# 140321_AriloTX_REV2_0_0.net
KiCad netlist of a schematic drawn in EAGLE
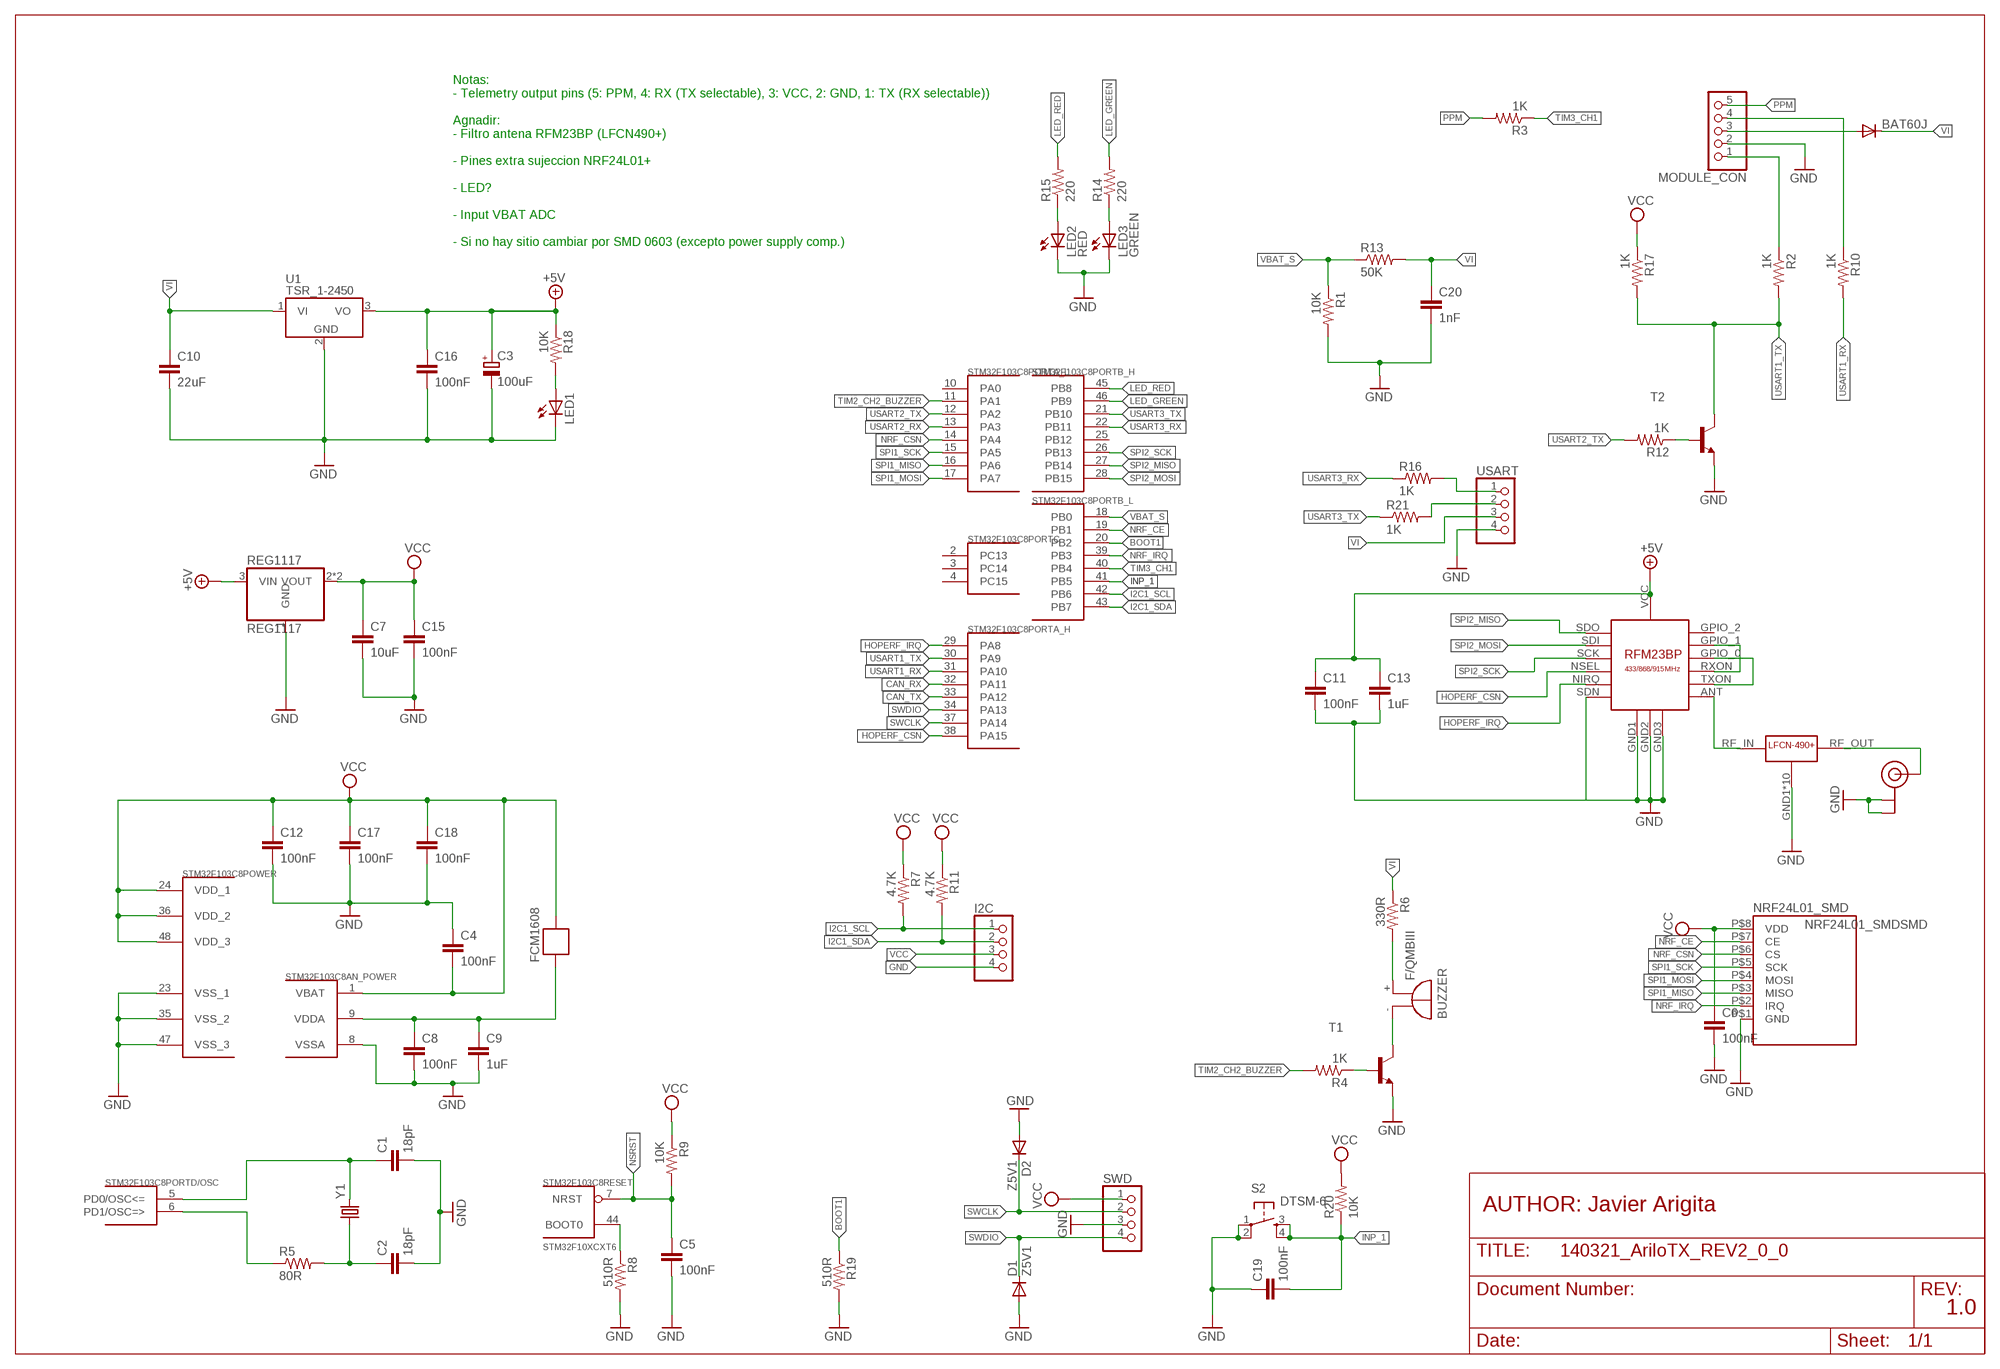
[diagram p0: schematic, sheet 1]

(export (version "E")
  (design (tool "Eeschema 10.0.6"))
  (components
    (comp (ref "BAT60J")
      (value "DIODE-SOD323-R")
      (footprint "eagle-import:SOD323-R")
      (libsource (lib "eagle-import") (part "DIODE-SOD323-R"))
    )
    (comp (ref "BUZZER")
      (value "F/QMBIII")
      (footprint "eagle-import:F_QMBIII")
      (libsource (lib "eagle-import") (part "F/QMBIII"))
    )
    (comp (ref "C1")
      (value "18pF")
      (footprint "eagle-import:C0805")
      (libsource (lib "eagle-import") (part "C-EUC0805"))
    )
    (comp (ref "C2")
      (value "18pF")
      (footprint "eagle-import:C0805")
      (libsource (lib "eagle-import") (part "C-EUC0805"))
    )
    (comp (ref "C3")
      (value "100uF")
      (footprint "eagle-import:SMC_B")
      (libsource (lib "eagle-import") (part "CPOL-EUSMCB"))
    )
    (comp (ref "C4")
      (value "100nF")
      (footprint "eagle-import:C0805")
      (libsource (lib "eagle-import") (part "C-EUC0805"))
    )
    (comp (ref "C5")
      (value "100nF")
      (footprint "eagle-import:C0805")
      (libsource (lib "eagle-import") (part "C-EUC0805"))
    )
    (comp (ref "C6")
      (value "100nF")
      (footprint "eagle-import:C0805")
      (libsource (lib "eagle-import") (part "C-EUC0805"))
    )
    (comp (ref "C7")
      (value "10uF")
      (footprint "eagle-import:C0805")
      (libsource (lib "eagle-import") (part "C-EUC0805"))
    )
    (comp (ref "C8")
      (value "100nF")
      (footprint "eagle-import:C0805")
      (libsource (lib "eagle-import") (part "C-EUC0805"))
    )
    (comp (ref "C9")
      (value "1uF")
      (footprint "eagle-import:C3216")
      (libsource (lib "eagle-import") (part "resistor_C-EUC3216"))
    )
    (comp (ref "C10")
      (value "22uF")
      (footprint "eagle-import:C3216")
      (libsource (lib "eagle-import") (part "resistor_C-EUC3216"))
    )
    (comp (ref "C11")
      (value "100nF")
      (footprint "eagle-import:C0805")
      (libsource (lib "eagle-import") (part "C-EUC0805"))
    )
    (comp (ref "C12")
      (value "100nF")
      (footprint "eagle-import:C0805")
      (libsource (lib "eagle-import") (part "C-EUC0805"))
    )
    (comp (ref "C13")
      (value "1uF")
      (footprint "eagle-import:C3216")
      (libsource (lib "eagle-import") (part "resistor_C-EUC3216"))
    )
    (comp (ref "C15")
      (value "100nF")
      (footprint "eagle-import:C0805")
      (libsource (lib "eagle-import") (part "C-EUC0805"))
    )
    (comp (ref "C16")
      (value "100nF")
      (footprint "eagle-import:C0805")
      (libsource (lib "eagle-import") (part "C-EUC0805"))
    )
    (comp (ref "C17")
      (value "100nF")
      (footprint "eagle-import:C0805")
      (libsource (lib "eagle-import") (part "C-EUC0805"))
    )
    (comp (ref "C18")
      (value "100nF")
      (footprint "eagle-import:C0805")
      (libsource (lib "eagle-import") (part "C-EUC0805"))
    )
    (comp (ref "C19")
      (value "100nF")
      (footprint "eagle-import:C0805")
      (libsource (lib "eagle-import") (part "C-EUC0805"))
    )
    (comp (ref "C20")
      (value "1nF")
      (footprint "eagle-import:C0805")
      (libsource (lib "eagle-import") (part "C-EUC0805"))
    )
    (comp (ref "D1")
      (value "Z5V1")
      (footprint "eagle-import:SOD323-R")
      (libsource (lib "eagle-import") (part "DIODE-SOD323-R"))
    )
    (comp (ref "D2")
      (value "Z5V1")
      (footprint "eagle-import:SOD323-R")
      (libsource (lib "eagle-import") (part "DIODE-SOD323-R"))
    )
    (comp (ref "FCM1608")
      (value "FERRITE-BEAD")
      (footprint "eagle-import:R0603")
      (libsource (lib "eagle-import") (part "FERRITE-BEAD"))
    )
    (comp (ref "I2C")
      (value "PINHD-1X4")
      (footprint "eagle-import:1X04")
      (libsource (lib "eagle-import") (part "PINHD-1X4"))
    )
    (comp (ref "LED1")
      (value "LED0805")
      (footprint "eagle-import:CHIPLED_0805")
      (libsource (lib "eagle-import") (part "LED0805"))
    )
    (comp (ref "LED2")
      (value "RED")
      (footprint "eagle-import:CHIP-LED0805")
      (libsource (lib "eagle-import") (part "LEDCHIP-LED0805"))
    )
    (comp (ref "LED3")
      (value "GREEN")
      (footprint "eagle-import:CHIP-LED0805")
      (libsource (lib "eagle-import") (part "LEDCHIP-LED0805"))
    )
    (comp (ref "MODULE_CON")
      (value "PINHD-1X5")
      (footprint "eagle-import:1X05")
      (libsource (lib "eagle-import") (part "PINHD-1X5"))
    )
    (comp (ref "NRF24L01_SMD")
      (value "NRF24L01_SMDSMD")
      (footprint "eagle-import:NRF24L01_SMD")
      (libsource (lib "eagle-import") (part "NRF24L01_SMDSMD"))
    )
    (comp (ref "R1")
      (value "10K")
      (footprint "eagle-import:R0805")
      (libsource (lib "eagle-import") (part "RESISTOR0805"))
    )
    (comp (ref "R2")
      (value "1K")
      (footprint "eagle-import:R0805")
      (libsource (lib "eagle-import") (part "RESISTOR0805"))
    )
    (comp (ref "R3")
      (value "1K")
      (footprint "eagle-import:R0805")
      (libsource (lib "eagle-import") (part "RESISTOR0805"))
    )
    (comp (ref "R4")
      (value "1K")
      (footprint "eagle-import:R0805")
      (libsource (lib "eagle-import") (part "RESISTOR0805"))
    )
    (comp (ref "R5")
      (value "80R")
      (footprint "eagle-import:R0805")
      (libsource (lib "eagle-import") (part "RESISTOR0805"))
    )
    (comp (ref "R6")
      (value "330R")
      (footprint "eagle-import:R0805")
      (libsource (lib "eagle-import") (part "RESISTOR0805"))
    )
    (comp (ref "R7")
      (value "4.7K")
      (footprint "eagle-import:R0805")
      (libsource (lib "eagle-import") (part "RESISTOR0805"))
    )
    (comp (ref "R8")
      (value "510R")
      (footprint "eagle-import:R0805")
      (libsource (lib "eagle-import") (part "RESISTOR0805"))
    )
    (comp (ref "R9")
      (value "10K")
      (footprint "eagle-import:R0805")
      (libsource (lib "eagle-import") (part "RESISTOR0805"))
    )
    (comp (ref "R10")
      (value "1K")
      (footprint "eagle-import:R0805")
      (libsource (lib "eagle-import") (part "RESISTOR0805"))
    )
    (comp (ref "R11")
      (value "4.7K")
      (footprint "eagle-import:R0805")
      (libsource (lib "eagle-import") (part "RESISTOR0805"))
    )
    (comp (ref "R12")
      (value "1K")
      (footprint "eagle-import:R0805")
      (libsource (lib "eagle-import") (part "RESISTOR0805"))
    )
    (comp (ref "R13")
      (value "50K")
      (footprint "eagle-import:R0805")
      (libsource (lib "eagle-import") (part "RESISTOR0805"))
    )
    (comp (ref "R14")
      (value "220")
      (footprint "eagle-import:R0805")
      (libsource (lib "eagle-import") (part "RESISTOR0805"))
    )
    (comp (ref "R15")
      (value "220")
      (footprint "eagle-import:R0805")
      (libsource (lib "eagle-import") (part "RESISTOR0805"))
    )
    (comp (ref "R16")
      (value "1K")
      (footprint "eagle-import:R0805")
      (libsource (lib "eagle-import") (part "RESISTOR0805"))
    )
    (comp (ref "R17")
      (value "1K")
      (footprint "eagle-import:R0805")
      (libsource (lib "eagle-import") (part "RESISTOR0805"))
    )
    (comp (ref "R18")
      (value "10K")
      (footprint "eagle-import:R0805")
      (libsource (lib "eagle-import") (part "RESISTOR0805"))
    )
    (comp (ref "R19")
      (value "510R")
      (footprint "eagle-import:R0805")
      (libsource (lib "eagle-import") (part "RESISTOR0805"))
    )
    (comp (ref "R20")
      (value "10K")
      (footprint "eagle-import:R0805")
      (libsource (lib "eagle-import") (part "RESISTOR0805"))
    )
    (comp (ref "R21")
      (value "1K")
      (footprint "eagle-import:R0805")
      (libsource (lib "eagle-import") (part "RESISTOR0805"))
    )
    (comp (ref "REG1117")
      (value "REG1117")
      (footprint "eagle-import:SOT223")
      (libsource (lib "eagle-import") (part "REG1117"))
    )
    (comp (ref "S2")
      (value "DTSM-6")
      (footprint "eagle-import:DTSM-6")
      (libsource (lib "eagle-import") (part "DTSM-6"))
    )
    (comp (ref "STM32F103C8")
      (value "STM32F10XCXT6")
      (footprint "eagle-import:TQFP48")
      (libsource (lib "eagle-import") (part "STM32F10XCXT6"))
    )
    (comp (ref "SWD")
      (value "PINHD-1X4")
      (footprint "eagle-import:1X04")
      (libsource (lib "eagle-import") (part "PINHD-1X4"))
    )
    (comp (ref "T1")
      (value "BC848-NPN-SOT23-BEC")
      (footprint "eagle-import:SOT23-BEC")
      (libsource (lib "eagle-import") (part "-NPN-SOT23-BECBC848"))
    )
    (comp (ref "T2")
      (value "BC848-NPN-SOT23-BEC")
      (footprint "eagle-import:SOT23-BEC")
      (libsource (lib "eagle-import") (part "-NPN-SOT23-BECBC848"))
    )
    (comp (ref "U$1")
      (value "RFM23BP")
      (footprint "eagle-import:RFM23BP")
      (libsource (lib "eagle-import") (part "RFM23BP"))
    )
    (comp (ref "U$2")
      (value "LFCN490+")
      (footprint "eagle-import:LFCN490+")
      (libsource (lib "eagle-import") (part "LFCN490+"))
    )
    (comp (ref "U$3")
      (value "U.FL")
      (footprint "eagle-import:U.FL")
      (libsource (lib "eagle-import") (part "U.FL"))
    )
    (comp (ref "U1")
      (value "TSR_1-2450")
      (footprint "eagle-import:TSR-1")
      (libsource (lib "eagle-import") (part "TSR_1-2450"))
    )
    (comp (ref "USART")
      (value "PINHD-1X4")
      (footprint "eagle-import:1X04")
      (libsource (lib "eagle-import") (part "PINHD-1X4"))
    )
    (comp (ref "Y1")
      (value "CRYSTAL5X3")
      (footprint "eagle-import:CRYSTAL-SMD-5X3")
      (libsource (lib "eagle-import") (part "CRYSTAL5X3"))
    )
  )
  (nets
    (net (code "1") (name "+5V") (class "Default")
      (node (ref "C11") (pin "1") (pinfunction "1_1") (pintype "passive"))
      (node (ref "C13") (pin "1") (pinfunction "1_1") (pintype "passive"))
      (node (ref "C16") (pin "1") (pinfunction "1_1") (pintype "passive"))
      (node (ref "C3") (pin "+") (pinfunction "+_+") (pintype "passive"))
      (node (ref "R18") (pin "1") (pinfunction "1_1") (pintype "passive"))
      (node (ref "REG1117") (pin "3") (pinfunction "VIN_3") (pintype "input"))
      (node (ref "U$1") (pin "VCC") (pinfunction "VCC_VCC") (pintype "power_in"))
      (node (ref "U1") (pin "3") (pinfunction "VO_3") (pintype "power_in"))
    )
    (net (code "2") (name "BOOT1") (class "Default")
      (node (ref "R19") (pin "1") (pinfunction "1_1") (pintype "passive"))
      (node (ref "STM32F103C8") (pin "20") (pinfunction "PB2_20") (pintype "bidirectional"))
    )
    (net (code "3") (name "CAN_RX") (class "Default")
      (node (ref "STM32F103C8") (pin "32") (pinfunction "PA11_32") (pintype "bidirectional"))
    )
    (net (code "4") (name "CAN_TX") (class "Default")
      (node (ref "STM32F103C8") (pin "33") (pinfunction "PA12_33") (pintype "bidirectional"))
    )
    (net (code "5") (name "GND") (class "Default")
      (node (ref "C1") (pin "2") (pinfunction "2_2") (pintype "passive"))
      (node (ref "C10") (pin "2") (pinfunction "2_2") (pintype "passive"))
      (node (ref "C11") (pin "2") (pinfunction "2_2") (pintype "passive"))
      (node (ref "C12") (pin "2") (pinfunction "2_2") (pintype "passive"))
      (node (ref "C13") (pin "2") (pinfunction "2_2") (pintype "passive"))
      (node (ref "C15") (pin "2") (pinfunction "2_2") (pintype "passive"))
      (node (ref "C16") (pin "2") (pinfunction "2_2") (pintype "passive"))
      (node (ref "C17") (pin "2") (pinfunction "2_2") (pintype "passive"))
      (node (ref "C18") (pin "2") (pinfunction "2_2") (pintype "passive"))
      (node (ref "C19") (pin "1") (pinfunction "1_1") (pintype "passive"))
      (node (ref "C2") (pin "2") (pinfunction "2_2") (pintype "passive"))
      (node (ref "C20") (pin "2") (pinfunction "2_2") (pintype "passive"))
      (node (ref "C3") (pin "-") (pinfunction "-_-") (pintype "passive"))
      (node (ref "C4") (pin "1") (pinfunction "1_1") (pintype "passive"))
      (node (ref "C5") (pin "2") (pinfunction "2_2") (pintype "passive"))
      (node (ref "C6") (pin "2") (pinfunction "2_2") (pintype "passive"))
      (node (ref "C7") (pin "2") (pinfunction "2_2") (pintype "passive"))
      (node (ref "C8") (pin "2") (pinfunction "2_2") (pintype "passive"))
      (node (ref "C9") (pin "2") (pinfunction "2_2") (pintype "passive"))
      (node (ref "D1") (pin "A") (pinfunction "A_A") (pintype "passive"))
      (node (ref "D2") (pin "A") (pinfunction "A_A") (pintype "passive"))
      (node (ref "I2C") (pin "4") (pinfunction "4_4") (pintype "passive"))
      (node (ref "LED1") (pin "C") (pinfunction "C_C") (pintype "passive"))
      (node (ref "LED2") (pin "C") (pinfunction "C_C") (pintype "passive"))
      (node (ref "LED3") (pin "C") (pinfunction "C_C") (pintype "passive"))
      (node (ref "MODULE_CON") (pin "2") (pinfunction "2_2") (pintype "passive"))
      (node (ref "NRF24L01_SMD") (pin "P$1") (pinfunction "GND_P$1") (pintype "power_in"))
      (node (ref "R1") (pin "2") (pinfunction "2_2") (pintype "passive"))
      (node (ref "R19") (pin "2") (pinfunction "2_2") (pintype "passive"))
      (node (ref "R8") (pin "2") (pinfunction "2_2") (pintype "passive"))
      (node (ref "REG1117") (pin "1") (pinfunction "GND_1") (pintype "power_in"))
      (node (ref "S2") (pin "1") (pinfunction "1_1") (pintype "passive"))
      (node (ref "S2") (pin "2") (pinfunction "2_2") (pintype "passive"))
      (node (ref "STM32F103C8") (pin "23") (pinfunction "VSS_1_23") (pintype "power_in"))
      (node (ref "STM32F103C8") (pin "35") (pinfunction "VSS_2_35") (pintype "power_in"))
      (node (ref "STM32F103C8") (pin "47") (pinfunction "VSS_3_47") (pintype "power_in"))
      (node (ref "STM32F103C8") (pin "8") (pinfunction "VSSA_8") (pintype "power_in"))
      (node (ref "SWD") (pin "3") (pinfunction "3_3") (pintype "passive"))
      (node (ref "T1") (pin "E") (pinfunction "E_E") (pintype "passive"))
      (node (ref "T2") (pin "E") (pinfunction "E_E") (pintype "passive"))
      (node (ref "U$1") (pin "GND1") (pinfunction "GND1_GND1") (pintype "power_in"))
      (node (ref "U$1") (pin "GND2") (pinfunction "GND2_GND2") (pintype "power_in"))
      (node (ref "U$1") (pin "GND3") (pinfunction "GND3_GND3") (pintype "power_in"))
      (node (ref "U$1") (pin "SDN") (pinfunction "SDN_SDN") (pintype "bidirectional"))
      (node (ref "U$2") (pin "GND1") (pinfunction "GND_GND1") (pintype "bidirectional"))
      (node (ref "U$2") (pin "GND10") (pinfunction "GND_GND10") (pintype "bidirectional"))
      (node (ref "U$2") (pin "GND2") (pinfunction "GND_GND2") (pintype "bidirectional"))
      (node (ref "U$2") (pin "GND3") (pinfunction "GND_GND3") (pintype "bidirectional"))
      (node (ref "U$2") (pin "GND4") (pinfunction "GND_GND4") (pintype "bidirectional"))
      (node (ref "U$2") (pin "GND5") (pinfunction "GND_GND5") (pintype "bidirectional"))
      (node (ref "U$2") (pin "GND6") (pinfunction "GND_GND6") (pintype "bidirectional"))
      (node (ref "U$2") (pin "GND7") (pinfunction "GND_GND7") (pintype "bidirectional"))
      (node (ref "U$2") (pin "GND8") (pinfunction "GND_GND8") (pintype "bidirectional"))
      (node (ref "U$2") (pin "GND9") (pinfunction "GND_GND9") (pintype "bidirectional"))
      (node (ref "U$3") (pin "P$1") (pinfunction "GND_P$1") (pintype "bidirectional"))
      (node (ref "U$3") (pin "P$2") (pinfunction "GND_P$2") (pintype "bidirectional"))
      (node (ref "U1") (pin "2") (pinfunction "GND_2") (pintype "power_in"))
      (node (ref "USART") (pin "4") (pinfunction "4_4") (pintype "passive"))
    )
    (net (code "6") (name "HOPERF_CSN") (class "Default")
      (node (ref "STM32F103C8") (pin "38") (pinfunction "PA15_38") (pintype "bidirectional"))
      (node (ref "U$1") (pin "NSEL") (pinfunction "NSEL_NSEL") (pintype "bidirectional"))
    )
    (net (code "7") (name "HOPERF_IRQ") (class "Default")
      (node (ref "STM32F103C8") (pin "29") (pinfunction "PA8_29") (pintype "bidirectional"))
      (node (ref "U$1") (pin "NIRQ") (pinfunction "NIRQ_NIRQ") (pintype "bidirectional"))
    )
    (net (code "8") (name "I2C1_SCL") (class "Default")
      (node (ref "I2C") (pin "1") (pinfunction "1_1") (pintype "passive"))
      (node (ref "R7") (pin "2") (pinfunction "2_2") (pintype "passive"))
      (node (ref "STM32F103C8") (pin "42") (pinfunction "PB6_42") (pintype "bidirectional"))
    )
    (net (code "9") (name "I2C1_SDA") (class "Default")
      (node (ref "I2C") (pin "2") (pinfunction "2_2") (pintype "passive"))
      (node (ref "R11") (pin "2") (pinfunction "2_2") (pintype "passive"))
      (node (ref "STM32F103C8") (pin "43") (pinfunction "PB7_43") (pintype "bidirectional"))
    )
    (net (code "10") (name "INP_1") (class "Default")
      (node (ref "C19") (pin "2") (pinfunction "2_2") (pintype "passive"))
      (node (ref "R20") (pin "1") (pinfunction "1_1") (pintype "passive"))
      (node (ref "S2") (pin "3") (pinfunction "3_3") (pintype "passive"))
      (node (ref "S2") (pin "4") (pinfunction "4_4") (pintype "passive"))
      (node (ref "STM32F103C8") (pin "41") (pinfunction "PB5_41") (pintype "bidirectional"))
    )
    (net (code "11") (name "LED_GREEN") (class "Default")
      (node (ref "R14") (pin "2") (pinfunction "2_2") (pintype "passive"))
      (node (ref "STM32F103C8") (pin "46") (pinfunction "PB9_46") (pintype "bidirectional"))
    )
    (net (code "12") (name "LED_RED") (class "Default")
      (node (ref "R15") (pin "2") (pinfunction "2_2") (pintype "passive"))
      (node (ref "STM32F103C8") (pin "45") (pinfunction "PB8_45") (pintype "bidirectional"))
    )
    (net (code "13") (name "NRF_CE") (class "Default")
      (node (ref "NRF24L01_SMD") (pin "P$7") (pinfunction "CE_P$7") (pintype "input"))
      (node (ref "STM32F103C8") (pin "19") (pinfunction "PB1_19") (pintype "bidirectional"))
    )
    (net (code "14") (name "NRF_CSN") (class "Default")
      (node (ref "NRF24L01_SMD") (pin "P$6") (pinfunction "CS_P$6") (pintype "input"))
      (node (ref "STM32F103C8") (pin "14") (pinfunction "PA4_14") (pintype "bidirectional"))
    )
    (net (code "15") (name "NRF_IRQ") (class "Default")
      (node (ref "NRF24L01_SMD") (pin "P$2") (pinfunction "IRQ_P$2") (pintype "output"))
      (node (ref "STM32F103C8") (pin "39") (pinfunction "PB3_39") (pintype "bidirectional"))
    )
    (net (code "16") (name "NSRST") (class "Default")
      (node (ref "C5") (pin "1") (pinfunction "1_1") (pintype "passive"))
      (node (ref "R9") (pin "2") (pinfunction "2_2") (pintype "passive"))
      (node (ref "STM32F103C8") (pin "7") (pinfunction "NRST_7") (pintype "input"))
    )
    (net (code "17") (name "Net-(BAT60J-PadA)") (class "Default")
      (node (ref "BAT60J") (pin "A") (pinfunction "A_A") (pintype "passive"))
      (node (ref "MODULE_CON") (pin "3") (pinfunction "3_3") (pintype "passive"))
    )
    (net (code "18") (name "Net-(BUZZER-+)") (class "Default")
      (node (ref "BUZZER") (pin "-") (pinfunction "+_-") (pintype "passive"))
      (node (ref "T1") (pin "C") (pinfunction "C_C") (pintype "passive"))
    )
    (net (code "19") (name "Net-(BUZZER--)") (class "Default")
      (node (ref "BUZZER") (pin "+") (pinfunction "-_+") (pintype "passive"))
      (node (ref "R6") (pin "2") (pinfunction "2_2") (pintype "passive"))
    )
    (net (code "20") (name "Net-(C2-Pad1)") (class "Default")
      (node (ref "C2") (pin "1") (pinfunction "1_1") (pintype "passive"))
      (node (ref "R5") (pin "2") (pinfunction "2_2") (pintype "passive"))
      (node (ref "Y1") (pin "1") (pinfunction "1_1") (pintype "passive"))
    )
    (net (code "21") (name "Net-(FCM1608-P$2)") (class "Default")
      (node (ref "C8") (pin "1") (pinfunction "1_1") (pintype "passive"))
      (node (ref "C9") (pin "1") (pinfunction "1_1") (pintype "passive"))
      (node (ref "FCM1608") (pin "2") (pinfunction "P$2_2") (pintype "bidirectional"))
      (node (ref "STM32F103C8") (pin "9") (pinfunction "VDDA_9") (pintype "power_in"))
    )
    (net (code "22") (name "Net-(LED1-PadA)") (class "Default")
      (node (ref "LED1") (pin "A") (pinfunction "A_A") (pintype "passive"))
      (node (ref "R18") (pin "2") (pinfunction "2_2") (pintype "passive"))
    )
    (net (code "23") (name "Net-(LED2-PadA)") (class "Default")
      (node (ref "LED2") (pin "A") (pinfunction "A_A") (pintype "passive"))
      (node (ref "R15") (pin "1") (pinfunction "1_1") (pintype "passive"))
    )
    (net (code "24") (name "Net-(LED3-PadA)") (class "Default")
      (node (ref "LED3") (pin "A") (pinfunction "A_A") (pintype "passive"))
      (node (ref "R14") (pin "1") (pinfunction "1_1") (pintype "passive"))
    )
    (net (code "25") (name "Net-(MODULE_CON-Pad1)") (class "Default")
      (node (ref "MODULE_CON") (pin "1") (pinfunction "1_1") (pintype "passive"))
      (node (ref "R2") (pin "1") (pinfunction "1_1") (pintype "passive"))
    )
    (net (code "26") (name "Net-(MODULE_CON-Pad4)") (class "Default")
      (node (ref "MODULE_CON") (pin "4") (pinfunction "4_4") (pintype "passive"))
      (node (ref "R10") (pin "1") (pinfunction "1_1") (pintype "passive"))
    )
    (net (code "27") (name "Net-(R4-Pad1)") (class "Default")
      (node (ref "R4") (pin "1") (pinfunction "1_1") (pintype "passive"))
      (node (ref "T1") (pin "B") (pinfunction "B_B") (pintype "passive"))
    )
    (net (code "28") (name "Net-(R12-Pad1)") (class "Default")
      (node (ref "R12") (pin "1") (pinfunction "1_1") (pintype "passive"))
      (node (ref "T2") (pin "B") (pinfunction "B_B") (pintype "passive"))
    )
    (net (code "29") (name "Net-(R16-Pad2)") (class "Default")
      (node (ref "R16") (pin "2") (pinfunction "2_2") (pintype "passive"))
      (node (ref "USART") (pin "1") (pinfunction "1_1") (pintype "passive"))
    )
    (net (code "30") (name "Net-(R21-Pad2)") (class "Default")
      (node (ref "R21") (pin "2") (pinfunction "2_2") (pintype "passive"))
      (node (ref "USART") (pin "2") (pinfunction "2_2") (pintype "passive"))
    )
    (net (code "31") (name "Net-(STM32F103C8G-PD0{slash}OSC<=)") (class "Default")
      (node (ref "C1") (pin "1") (pinfunction "1_1") (pintype "passive"))
      (node (ref "STM32F103C8") (pin "5") (pinfunction "PD0/OSC<=_5") (pintype "bidirectional"))
      (node (ref "Y1") (pin "3") (pinfunction "2_3") (pintype "passive"))
    )
    (net (code "32") (name "Net-(STM32F103C8G-PD1{slash}OSC=>)") (class "Default")
      (node (ref "R5") (pin "1") (pinfunction "1_1") (pintype "passive"))
      (node (ref "STM32F103C8") (pin "6") (pinfunction "PD1/OSC=>_6") (pintype "bidirectional"))
    )
    (net (code "33") (name "Net-(STM32F103C8I-BOOT0)") (class "Default")
      (node (ref "R8") (pin "1") (pinfunction "1_1") (pintype "passive"))
      (node (ref "STM32F103C8") (pin "44") (pinfunction "BOOT0_44") (pintype "input"))
    )
    (net (code "34") (name "Net-(U$1-PadGPIO_0)") (class "Default")
      (node (ref "U$1") (pin "GPIO_0") (pinfunction "GPIO_0_GPIO_0") (pintype "bidirectional"))
      (node (ref "U$1") (pin "TXON") (pinfunction "TXON_TXON") (pintype "bidirectional"))
    )
    (net (code "35") (name "Net-(U$1-PadGPIO_1)") (class "Default")
      (node (ref "U$1") (pin "GPIO_1") (pinfunction "GPIO_1_GPIO_1") (pintype "bidirectional"))
      (node (ref "U$1") (pin "RXON") (pinfunction "RXON_RXON") (pintype "bidirectional"))
    )
    (net (code "36") (name "Net-(U$2-RF_INP)") (class "Default")
      (node (ref "U$1") (pin "ANT") (pinfunction "ANT_ANT") (pintype "bidirectional"))
      (node (ref "U$2") (pin "RF_IN") (pinfunction "RF_INP_RF_IN") (pintype "bidirectional"))
    )
    (net (code "37") (name "Net-(U$2-RF_OUTP)") (class "Default")
      (node (ref "U$2") (pin "RF_OUT") (pinfunction "RF_OUTP_RF_OUT") (pintype "bidirectional"))
      (node (ref "U$3") (pin "P$3") (pinfunction "SIGNAL_P$3") (pintype "bidirectional"))
    )
    (net (code "38") (name "PPM") (class "Default")
      (node (ref "MODULE_CON") (pin "5") (pinfunction "5_5") (pintype "passive"))
      (node (ref "R3") (pin "2") (pinfunction "2_2") (pintype "passive"))
    )
    (net (code "39") (name "SPI1_MISO") (class "Default")
      (node (ref "NRF24L01_SMD") (pin "P$3") (pinfunction "MISO_P$3") (pintype "output"))
      (node (ref "STM32F103C8") (pin "16") (pinfunction "PA6_16") (pintype "bidirectional"))
    )
    (net (code "40") (name "SPI1_MOSI") (class "Default")
      (node (ref "NRF24L01_SMD") (pin "P$4") (pinfunction "MOSI_P$4") (pintype "input"))
      (node (ref "STM32F103C8") (pin "17") (pinfunction "PA7_17") (pintype "bidirectional"))
    )
    (net (code "41") (name "SPI1_SCK") (class "Default")
      (node (ref "NRF24L01_SMD") (pin "P$5") (pinfunction "SCK_P$5") (pintype "input"))
      (node (ref "STM32F103C8") (pin "15") (pinfunction "PA5_15") (pintype "bidirectional"))
    )
    (net (code "42") (name "SPI2_MISO") (class "Default")
      (node (ref "STM32F103C8") (pin "27") (pinfunction "PB14_27") (pintype "bidirectional"))
      (node (ref "U$1") (pin "SDO") (pinfunction "SDO_SDO") (pintype "bidirectional"))
    )
    (net (code "43") (name "SPI2_MOSI") (class "Default")
      (node (ref "STM32F103C8") (pin "28") (pinfunction "PB15_28") (pintype "bidirectional"))
      (node (ref "U$1") (pin "SDI") (pinfunction "SDI_SDI") (pintype "bidirectional"))
    )
    (net (code "44") (name "SPI2_SCK") (class "Default")
      (node (ref "STM32F103C8") (pin "26") (pinfunction "PB13_26") (pintype "bidirectional"))
      (node (ref "U$1") (pin "SCK") (pinfunction "SCK_SCK") (pintype "bidirectional"))
    )
    (net (code "45") (name "SWCLK") (class "Default")
      (node (ref "D2") (pin "C") (pinfunction "C_C") (pintype "passive"))
      (node (ref "STM32F103C8") (pin "37") (pinfunction "PA14_37") (pintype "bidirectional"))
      (node (ref "SWD") (pin "2") (pinfunction "2_2") (pintype "passive"))
    )
    (net (code "46") (name "SWDIO") (class "Default")
      (node (ref "D1") (pin "C") (pinfunction "C_C") (pintype "passive"))
      (node (ref "STM32F103C8") (pin "34") (pinfunction "PA13_34") (pintype "bidirectional"))
      (node (ref "SWD") (pin "4") (pinfunction "4_4") (pintype "passive"))
    )
    (net (code "47") (name "TIM2_CH2_BUZZER") (class "Default")
      (node (ref "R4") (pin "2") (pinfunction "2_2") (pintype "passive"))
      (node (ref "STM32F103C8") (pin "11") (pinfunction "PA1_11") (pintype "bidirectional"))
    )
    (net (code "48") (name "TIM3_CH1") (class "Default")
      (node (ref "R3") (pin "1") (pinfunction "1_1") (pintype "passive"))
      (node (ref "STM32F103C8") (pin "40") (pinfunction "PB4_40") (pintype "bidirectional"))
    )
    (net (code "49") (name "USART1_RX") (class "Default")
      (node (ref "R10") (pin "2") (pinfunction "2_2") (pintype "passive"))
      (node (ref "STM32F103C8") (pin "31") (pinfunction "PA10_31") (pintype "bidirectional"))
    )
    (net (code "50") (name "USART1_TX") (class "Default")
      (node (ref "R17") (pin "2") (pinfunction "2_2") (pintype "passive"))
      (node (ref "R2") (pin "2") (pinfunction "2_2") (pintype "passive"))
      (node (ref "STM32F103C8") (pin "30") (pinfunction "PA9_30") (pintype "bidirectional"))
      (node (ref "T2") (pin "C") (pinfunction "C_C") (pintype "passive"))
    )
    (net (code "51") (name "USART2_RX") (class "Default")
      (node (ref "STM32F103C8") (pin "13") (pinfunction "PA3_13") (pintype "bidirectional"))
    )
    (net (code "52") (name "USART2_TX") (class "Default")
      (node (ref "R12") (pin "2") (pinfunction "2_2") (pintype "passive"))
      (node (ref "STM32F103C8") (pin "12") (pinfunction "PA2_12") (pintype "bidirectional"))
    )
    (net (code "53") (name "USART3_RX") (class "Default")
      (node (ref "R16") (pin "1") (pinfunction "1_1") (pintype "passive"))
      (node (ref "STM32F103C8") (pin "22") (pinfunction "PB11_22") (pintype "bidirectional"))
    )
    (net (code "54") (name "USART3_TX") (class "Default")
      (node (ref "R21") (pin "1") (pinfunction "1_1") (pintype "passive"))
      (node (ref "STM32F103C8") (pin "21") (pinfunction "PB10_21") (pintype "bidirectional"))
    )
    (net (code "55") (name "VBAT_S") (class "Default")
      (node (ref "R1") (pin "1") (pinfunction "1_1") (pintype "passive"))
      (node (ref "R13") (pin "1") (pinfunction "1_1") (pintype "passive"))
      (node (ref "STM32F103C8") (pin "18") (pinfunction "PB0_18") (pintype "bidirectional"))
    )
    (net (code "56") (name "VCC") (class "Default")
      (node (ref "C12") (pin "1") (pinfunction "1_1") (pintype "passive"))
      (node (ref "C15") (pin "1") (pinfunction "1_1") (pintype "passive"))
      (node (ref "C17") (pin "1") (pinfunction "1_1") (pintype "passive"))
      (node (ref "C18") (pin "1") (pinfunction "1_1") (pintype "passive"))
      (node (ref "C4") (pin "2") (pinfunction "2_2") (pintype "passive"))
      (node (ref "C6") (pin "1") (pinfunction "1_1") (pintype "passive"))
      (node (ref "C7") (pin "1") (pinfunction "1_1") (pintype "passive"))
      (node (ref "FCM1608") (pin "1") (pinfunction "P$1_1") (pintype "bidirectional"))
      (node (ref "I2C") (pin "3") (pinfunction "3_3") (pintype "passive"))
      (node (ref "NRF24L01_SMD") (pin "P$8") (pinfunction "VDD_P$8") (pintype "bidirectional"))
      (node (ref "R11") (pin "1") (pinfunction "1_1") (pintype "passive"))
      (node (ref "R17") (pin "1") (pinfunction "1_1") (pintype "passive"))
      (node (ref "R20") (pin "2") (pinfunction "2_2") (pintype "passive"))
      (node (ref "R7") (pin "1") (pinfunction "1_1") (pintype "passive"))
      (node (ref "R9") (pin "1") (pinfunction "1_1") (pintype "passive"))
      (node (ref "REG1117") (pin "2") (pinfunction "VOUT_2") (pintype "power_in"))
      (node (ref "REG1117") (pin "4") (pinfunction "VOUT_4") (pintype "power_in"))
      (node (ref "STM32F103C8") (pin "1") (pinfunction "VBAT_1") (pintype "power_in"))
      (node (ref "STM32F103C8") (pin "24") (pinfunction "VDD_1_24") (pintype "power_in"))
      (node (ref "STM32F103C8") (pin "36") (pinfunction "VDD_2_36") (pintype "power_in"))
      (node (ref "STM32F103C8") (pin "48") (pinfunction "VDD_3_48") (pintype "power_in"))
      (node (ref "SWD") (pin "1") (pinfunction "1_1") (pintype "passive"))
    )
    (net (code "57") (name "VI") (class "Default")
      (node (ref "BAT60J") (pin "C") (pinfunction "C_C") (pintype "passive"))
      (node (ref "C10") (pin "1") (pinfunction "1_1") (pintype "passive"))
      (node (ref "C20") (pin "1") (pinfunction "1_1") (pintype "passive"))
      (node (ref "R13") (pin "2") (pinfunction "2_2") (pintype "passive"))
      (node (ref "R6") (pin "1") (pinfunction "1_1") (pintype "passive"))
      (node (ref "U1") (pin "1") (pinfunction "VI_1") (pintype "power_in"))
      (node (ref "USART") (pin "3") (pinfunction "3_3") (pintype "passive"))
    )
    (net (code "58") (name "unconnected-(STM32F103C8C-PA0-Pad10)") (class "Default")
      (node (ref "STM32F103C8") (pin "10") (pinfunction "PA0_10") (pintype "bidirectional"))
    )
    (net (code "59") (name "unconnected-(STM32F103C8D-PB12-Pad25)") (class "Default")
      (node (ref "STM32F103C8") (pin "25") (pinfunction "PB12_25") (pintype "bidirectional"))
    )
    (net (code "60") (name "unconnected-(STM32F103C8F-PC13-Pad2)") (class "Default")
      (node (ref "STM32F103C8") (pin "2") (pinfunction "PC13_2") (pintype "bidirectional"))
    )
    (net (code "61") (name "unconnected-(STM32F103C8F-PC14-Pad3)") (class "Default")
      (node (ref "STM32F103C8") (pin "3") (pinfunction "PC14_3") (pintype "bidirectional"))
    )
    (net (code "62") (name "unconnected-(STM32F103C8F-PC15-Pad4)") (class "Default")
      (node (ref "STM32F103C8") (pin "4") (pinfunction "PC15_4") (pintype "bidirectional"))
    )
    (net (code "63") (name "unconnected-(U$1-PadGPIO_2)") (class "Default")
      (node (ref "U$1") (pin "GPIO_2") (pinfunction "GPIO_2_GPIO_2") (pintype "bidirectional"))
    )
  )
)
